# Arak-ADC.net
KiCad netlist of a schematic drawn in Altium Designer
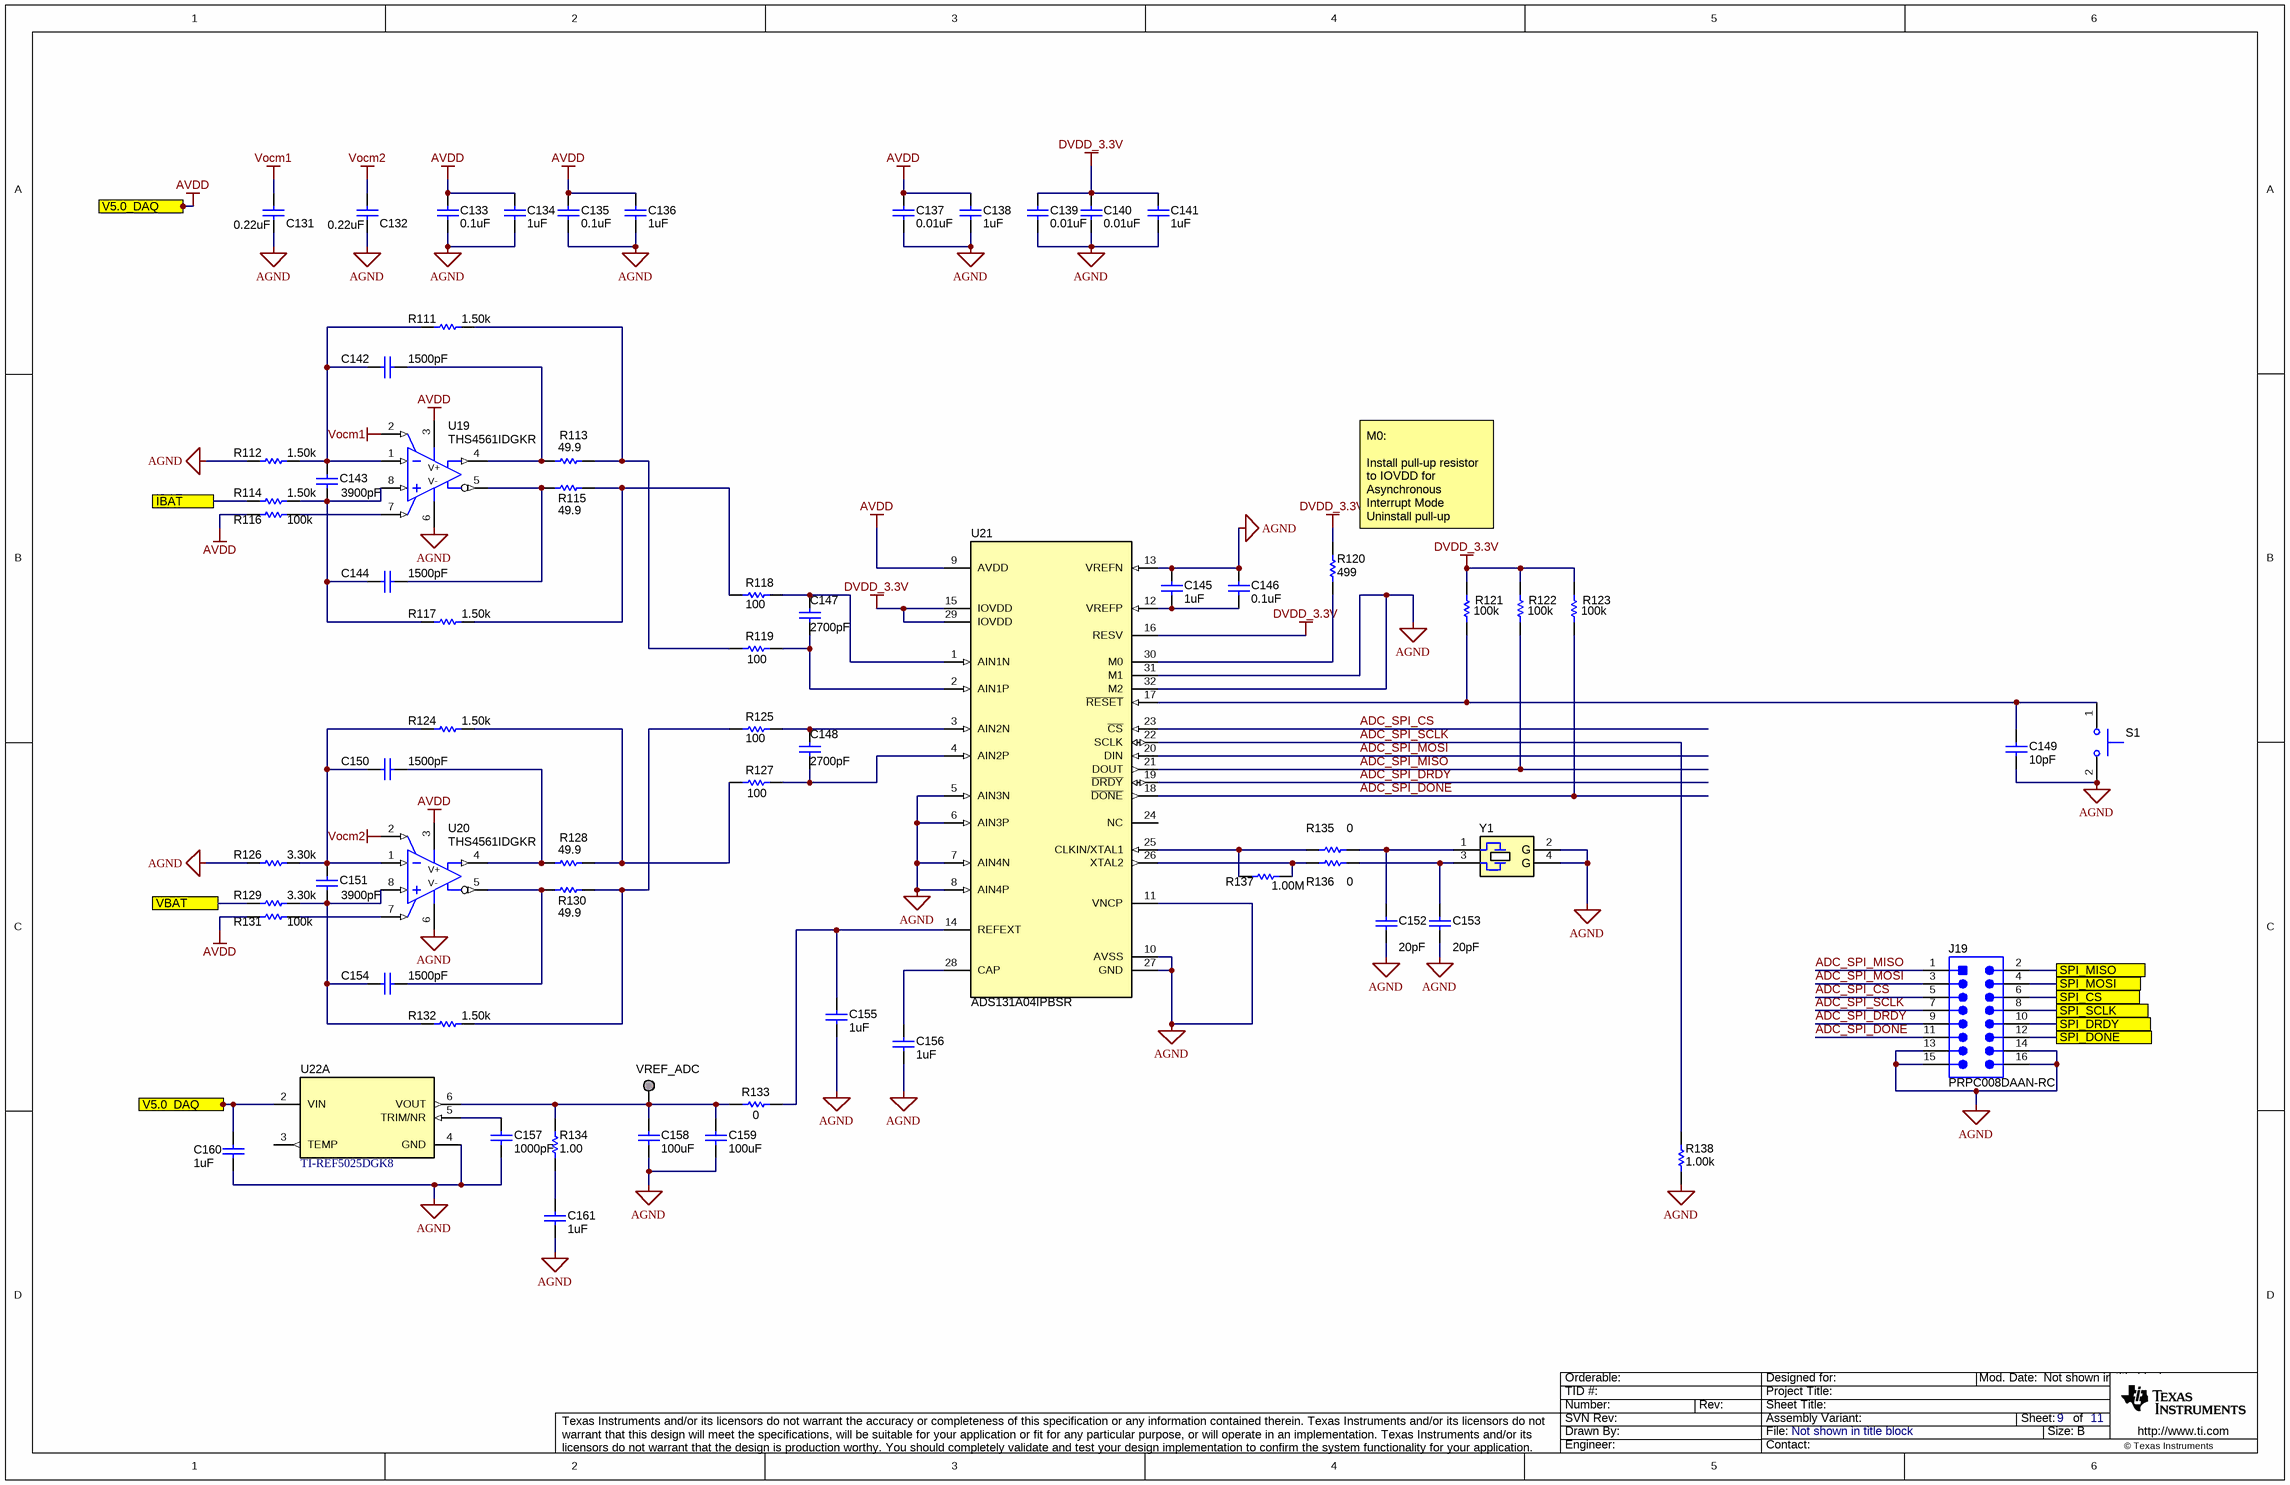
[diagram p0: Arak-ADC.SchDoc]

(export (version "E")
  (design (tool "Eeschema 10.0.6"))
  (components
    (comp (ref "C131")
      (value "Capacitor")
      (footprint "0603")
      (description "CAP, CERM, 0.22 uF, 16 V, +/- 10%, X7R, 0603")
      (fields
        (field (name "PARTNUMBER") "C0603C224K4RACTU")
        (field (name "VALUEDISPLAYED") "0.22uF")
        (field (name "MANUFACTURER") "Kemet")
        (field (name "PUBLISHER") "Texas Instruments")
      )
      (libsource (lib "Altium Vault - TI") (part "CMP-0006903-4"))
    )
    (comp (ref "C132")
      (value "Capacitor")
      (footprint "0603")
      (description "CAP, CERM, 0.22 uF, 16 V, +/- 10%, X7R, 0603")
      (fields
        (field (name "PARTNUMBER") "C0603C224K4RACTU")
        (field (name "VALUEDISPLAYED") "0.22uF")
        (field (name "MANUFACTURER") "Kemet")
        (field (name "PUBLISHER") "Texas Instruments")
      )
      (libsource (lib "Altium Vault - TI") (part "CMP-0006903-4"))
    )
    (comp (ref "C133")
      (value "Capacitor")
      (footprint "0603")
      (description "CAP, CERM, 0.1 uF, 25 V, +/- 5%, X7R, 0603")
      (fields
        (field (name "PARTNUMBER") "06033C104JAT2A")
        (field (name "VALUEDISPLAYED") "0.1uF")
        (field (name "MANUFACTURER") "AVX")
        (field (name "PUBLISHER") "Texas Instruments")
      )
      (libsource (lib "Altium Vault - TI") (part "CMP-0006752-5"))
    )
    (comp (ref "C134")
      (value "Capacitor")
      (footprint "0603")
      (description "CAP, CERM, 1 uF, 25 V, +/- 10%, X7R, 0603")
      (fields
        (field (name "PARTNUMBER") "GRM188R71E105KA12D")
        (field (name "VALUEDISPLAYED") "1uF")
        (field (name "MANUFACTURER") "MuRata")
        (field (name "PUBLISHER") "Texas Instruments")
      )
      (libsource (lib "Altium Vault - TI") (part "CMP-0007405-4"))
    )
    (comp (ref "C135")
      (value "Capacitor")
      (footprint "0603")
      (description "CAP, CERM, 0.1 uF, 25 V, +/- 5%, X7R, 0603")
      (fields
        (field (name "PARTNUMBER") "06033C104JAT2A")
        (field (name "VALUEDISPLAYED") "0.1uF")
        (field (name "MANUFACTURER") "AVX")
        (field (name "PUBLISHER") "Texas Instruments")
      )
      (libsource (lib "Altium Vault - TI") (part "CMP-0006752-5"))
    )
    (comp (ref "C136")
      (value "Capacitor")
      (footprint "0603")
      (description "CAP, CERM, 1 uF, 25 V, +/- 10%, X7R, 0603")
      (fields
        (field (name "PARTNUMBER") "GRM188R71E105KA12D")
        (field (name "VALUEDISPLAYED") "1uF")
        (field (name "MANUFACTURER") "MuRata")
        (field (name "PUBLISHER") "Texas Instruments")
      )
      (libsource (lib "Altium Vault - TI") (part "CMP-0007405-4"))
    )
    (comp (ref "C137")
      (value "Capacitor")
      (footprint "0603")
      (description "CAP, CERM, 0.01 uF, 100 V, +/- 10%, X7R, 0603")
      (fields
        (field (name "PARTNUMBER") "06031C103KAT2A")
        (field (name "VALUEDISPLAYED") "0.01uF")
        (field (name "MANUFACTURER") "AVX")
        (field (name "PUBLISHER") "Texas Instruments")
      )
      (libsource (lib "Altium Vault - TI") (part "CMP-0006727-4"))
    )
    (comp (ref "C138")
      (value "Capacitor")
      (footprint "0603")
      (description "CAP, CERM, 1 uF, 25 V, +/- 10%, X7R, 0603")
      (fields
        (field (name "PARTNUMBER") "GRM188R71E105KA12D")
        (field (name "VALUEDISPLAYED") "1uF")
        (field (name "MANUFACTURER") "MuRata")
        (field (name "PUBLISHER") "Texas Instruments")
      )
      (libsource (lib "Altium Vault - TI") (part "CMP-0007405-4"))
    )
    (comp (ref "C139")
      (value "Capacitor")
      (footprint "0603")
      (description "CAP, CERM, 0.01 uF, 100 V, +/- 10%, X7R, 0603")
      (fields
        (field (name "PARTNUMBER") "06031C103KAT2A")
        (field (name "VALUEDISPLAYED") "0.01uF")
        (field (name "MANUFACTURER") "AVX")
        (field (name "PUBLISHER") "Texas Instruments")
      )
      (libsource (lib "Altium Vault - TI") (part "CMP-0006727-4"))
    )
    (comp (ref "C140")
      (value "Capacitor")
      (footprint "0603")
      (description "CAP, CERM, 0.01 uF, 100 V, +/- 10%, X7R, 0603")
      (fields
        (field (name "PARTNUMBER") "06031C103KAT2A")
        (field (name "VALUEDISPLAYED") "0.01uF")
        (field (name "MANUFACTURER") "AVX")
        (field (name "PUBLISHER") "Texas Instruments")
      )
      (libsource (lib "Altium Vault - TI") (part "CMP-0006727-4"))
    )
    (comp (ref "C141")
      (value "Capacitor")
      (footprint "0603")
      (description "CAP, CERM, 1 uF, 25 V, +/- 10%, X7R, 0603")
      (fields
        (field (name "PARTNUMBER") "GRM188R71E105KA12D")
        (field (name "VALUEDISPLAYED") "1uF")
        (field (name "MANUFACTURER") "MuRata")
        (field (name "PUBLISHER") "Texas Instruments")
      )
      (libsource (lib "Altium Vault - TI") (part "CMP-0007405-4"))
    )
    (comp (ref "C142")
      (value "Capacitor")
      (footprint "0603")
      (description "CAP, CERM, 1500 pF, 100 V, +/- 5%, X7R, 0603")
      (fields
        (field (name "PARTNUMBER") "06031C152JAT2A")
        (field (name "VALUEDISPLAYED") "1500pF")
        (field (name "MANUFACTURER") "AVX")
        (field (name "PUBLISHER") "Texas Instruments")
      )
      (libsource (lib "Altium Vault - TI") (part "Capacitor"))
    )
    (comp (ref "C143")
      (value "GRM188R72A392KA01D")
      (footprint "0603")
      (description "CAP, CERM, 3900 pF, 100 V, +/- 10%, X7R, 0603")
      (fields
        (field (name "MANUFACTURER") "MuRata")
        (field (name "VALUEDISPLAYED") "3900pF")
        (field (name "PUBLISHER") "Texas Instruments")
      )
      (libsource (lib "Altium Vault - TI") (part "CMP-0007481-5"))
    )
    (comp (ref "C144")
      (value "Capacitor")
      (footprint "0603")
      (description "CAP, CERM, 1500 pF, 100 V, +/- 5%, X7R, 0603")
      (fields
        (field (name "PARTNUMBER") "06031C152JAT2A")
        (field (name "VALUEDISPLAYED") "1500pF")
        (field (name "MANUFACTURER") "AVX")
        (field (name "PUBLISHER") "Texas Instruments")
      )
      (libsource (lib "Altium Vault - TI") (part "Capacitor"))
    )
    (comp (ref "C145")
      (value "Capacitor")
      (footprint "0603")
      (description "CAP, CERM, 1 uF, 25 V, +/- 10%, X7R, 0603")
      (fields
        (field (name "PARTNUMBER") "GRM188R71E105KA12D")
        (field (name "VALUEDISPLAYED") "1uF")
        (field (name "MANUFACTURER") "MuRata")
        (field (name "PUBLISHER") "Texas Instruments")
      )
      (libsource (lib "Altium Vault - TI") (part "Capacitor"))
    )
    (comp (ref "C146")
      (value "Capacitor")
      (footprint "0603")
      (description "CAP, CERM, 0.1 uF, 25 V, +/- 5%, X7R, 0603")
      (fields
        (field (name "PARTNUMBER") "06033C104JAT2A")
        (field (name "VALUEDISPLAYED") "0.1uF")
        (field (name "MANUFACTURER") "AVX")
        (field (name "PUBLISHER") "Texas Instruments")
      )
      (libsource (lib "Altium Vault - TI") (part "Capacitor"))
    )
    (comp (ref "C147")
      (value "Capacitor")
      (footprint "0603")
      (description "CAP, CERM, 2700 pF, 50 V, +/- 5%, C0G/NP0, 0603")
      (fields
        (field (name "PARTNUMBER") "GRM1885C1H272JA01D")
        (field (name "VALUEDISPLAYED") "2700pF")
        (field (name "MANUFACTURER") "MuRata")
        (field (name "PUBLISHER") "Texas Instruments")
      )
      (libsource (lib "Altium Vault - TI") (part "Capacitor"))
    )
    (comp (ref "C148")
      (value "Capacitor")
      (footprint "0603")
      (description "CAP, CERM, 2700 pF, 50 V, +/- 5%, C0G/NP0, 0603")
      (fields
        (field (name "PARTNUMBER") "GRM1885C1H272JA01D")
        (field (name "VALUEDISPLAYED") "2700pF")
        (field (name "MANUFACTURER") "MuRata")
        (field (name "PUBLISHER") "Texas Instruments")
      )
      (libsource (lib "Altium Vault - TI") (part "Capacitor"))
    )
    (comp (ref "C149")
      (value "Capacitor")
      (footprint "0603")
      (description "CAP, CERM, 10 pF, 50 V, +/- 5%, C0G/NP0, 0603")
      (fields
        (field (name "PARTNUMBER") "06035A100JAT2A")
        (field (name "VALUEDISPLAYED") "10pF")
        (field (name "MANUFACTURER") "AVX")
        (field (name "PUBLISHER") "Texas Instruments")
      )
      (libsource (lib "Altium Vault - TI") (part "Capacitor"))
    )
    (comp (ref "C150")
      (value "Capacitor")
      (footprint "0603")
      (description "CAP, CERM, 1500 pF, 100 V, +/- 5%, X7R, 0603")
      (fields
        (field (name "PARTNUMBER") "06031C152JAT2A")
        (field (name "VALUEDISPLAYED") "1500pF")
        (field (name "MANUFACTURER") "AVX")
        (field (name "PUBLISHER") "Texas Instruments")
      )
      (libsource (lib "Altium Vault - TI") (part "Capacitor"))
    )
    (comp (ref "C151")
      (value "GRM188R72A392KA01D")
      (footprint "0603")
      (description "CAP, CERM, 3900 pF, 100 V, +/- 10%, X7R, 0603")
      (fields
        (field (name "MANUFACTURER") "MuRata")
        (field (name "VALUEDISPLAYED") "3900pF")
        (field (name "PUBLISHER") "Texas Instruments")
      )
      (libsource (lib "Altium Vault - TI") (part "CMP-0007481-5"))
    )
    (comp (ref "C152")
      (value "GRM1885C1H200JA01D")
      (footprint "0603")
      (description "CAP, CERM, 20 pF, 50 V, +/- 5%, C0G/NP0, 0603")
      (fields
        (field (name "MANUFACTURER") "MuRata")
        (field (name "VALUEDISPLAYED") "20pF")
        (field (name "PUBLISHER") "Texas Instruments")
      )
      (libsource (lib "Altium Vault - TI") (part "CMP-0007193-4"))
    )
    (comp (ref "C153")
      (value "GRM1885C1H200JA01D")
      (footprint "0603")
      (description "CAP, CERM, 20 pF, 50 V, +/- 5%, C0G/NP0, 0603")
      (fields
        (field (name "MANUFACTURER") "MuRata")
        (field (name "VALUEDISPLAYED") "20pF")
        (field (name "PUBLISHER") "Texas Instruments")
      )
      (libsource (lib "Altium Vault - TI") (part "CMP-0007193-4"))
    )
    (comp (ref "C154")
      (value "Capacitor")
      (footprint "0603")
      (description "CAP, CERM, 1500 pF, 100 V, +/- 5%, X7R, 0603")
      (fields
        (field (name "PARTNUMBER") "06031C152JAT2A")
        (field (name "VALUEDISPLAYED") "1500pF")
        (field (name "MANUFACTURER") "AVX")
        (field (name "PUBLISHER") "Texas Instruments")
      )
      (libsource (lib "Altium Vault - TI") (part "Capacitor"))
    )
    (comp (ref "C155")
      (value "Capacitor")
      (footprint "0603")
      (description "CAP, CERM, 1 uF, 25 V, +/- 10%, X7R, 0603")
      (fields
        (field (name "PARTNUMBER") "GRM188R71E105KA12D")
        (field (name "VALUEDISPLAYED") "1uF")
        (field (name "MANUFACTURER") "MuRata")
        (field (name "PUBLISHER") "Texas Instruments")
      )
      (libsource (lib "Altium Vault - TI") (part "Capacitor"))
    )
    (comp (ref "C156")
      (value "Capacitor")
      (footprint "0603")
      (description "CAP, CERM, 1 uF, 25 V, +/- 10%, X7R, 0603")
      (fields
        (field (name "PARTNUMBER") "GRM188R71E105KA12D")
        (field (name "VALUEDISPLAYED") "1uF")
        (field (name "MANUFACTURER") "MuRata")
        (field (name "PUBLISHER") "Texas Instruments")
      )
      (libsource (lib "Altium Vault - TI") (part "Capacitor"))
    )
    (comp (ref "C157")
      (value "Capacitor")
      (footprint "0603")
      (description "CAP, CERM, 1000 pF, 100 V, +/- 5%, X7R, 0603")
      (fields
        (field (name "PARTNUMBER") "06031C102JAT2A")
        (field (name "VALUEDISPLAYED") "1000pF")
        (field (name "MANUFACTURER") "AVX")
        (field (name "PUBLISHER") "Texas Instruments")
      )
      (libsource (lib "Altium Vault - TI") (part "Capacitor"))
    )
    (comp (ref "C158")
      (value "Capacitor")
      (footprint "1206_190")
      (description "CAP, CERM, 100 uF, 10 V, +/- 20%, X5R, 1206_190")
      (fields
        (field (name "PARTNUMBER") "C3216X5R1A107M160AC")
        (field (name "VALUEDISPLAYED") "100uF")
        (field (name "MANUFACTURER") "TDK")
        (field (name "PUBLISHER") "Texas Instruments")
      )
      (libsource (lib "Altium Vault - TI") (part "Capacitor"))
    )
    (comp (ref "C159")
      (value "Capacitor")
      (footprint "1206_190")
      (description "CAP, CERM, 100 uF, 10 V, +/- 20%, X5R, 1206_190")
      (fields
        (field (name "PARTNUMBER") "C3216X5R1A107M160AC")
        (field (name "VALUEDISPLAYED") "100uF")
        (field (name "MANUFACTURER") "TDK")
        (field (name "PUBLISHER") "Texas Instruments")
      )
      (libsource (lib "Altium Vault - TI") (part "Capacitor"))
    )
    (comp (ref "C160")
      (value "Capacitor")
      (footprint "0603")
      (description "CAP, CERM, 1 uF, 25 V, +/- 10%, X7R, 0603")
      (fields
        (field (name "PARTNUMBER") "GRM188R71E105KA12D")
        (field (name "VALUEDISPLAYED") "1uF")
        (field (name "MANUFACTURER") "MuRata")
        (field (name "PUBLISHER") "Texas Instruments")
      )
      (libsource (lib "Altium Vault - TI") (part "Capacitor"))
    )
    (comp (ref "C161")
      (value "Capacitor")
      (footprint "0603")
      (description "CAP, CERM, 1 uF, 25 V, +/- 10%, X7R, 0603")
      (fields
        (field (name "PARTNUMBER") "GRM188R71E105KA12D")
        (field (name "VALUEDISPLAYED") "1uF")
        (field (name "MANUFACTURER") "MuRata")
        (field (name "PUBLISHER") "Texas Instruments")
      )
      (libsource (lib "Altium Vault - TI") (part "Capacitor"))
    )
    (comp (ref "J19")
      (value "PRPC008DAAN-RC")
      (footprint "Sullins_xxxC008DAAN")
      (description "Header, 2.54mm, 8x2, Gold, TH")
      (fields
        (field (name "MANUFACTURER") "Sullins Connector Solutions")
        (field (name "PUBLISHER") "Texas Instruments")
      )
      (libsource (lib "Altium Vault - TI") (part "CMP-0054590-1"))
    )
    (comp (ref "R111")
      (value "RC0603FR-071K5L")
      (footprint "0603")
      (description "RES, 1.50 k, 1%, 0.1 W, 0603")
      (fields
        (field (name "MANUFACTURER") "Yageo America")
        (field (name "VALUEDISPLAYED") "1.50k")
        (field (name "PUBLISHER") "Texas Instruments")
      )
      (libsource (lib "Altium Vault - TI") (part "CMP-0022883-3"))
    )
    (comp (ref "R112")
      (value "RC0603FR-071K5L")
      (footprint "0603")
      (description "RES, 1.50 k, 1%, 0.1 W, 0603")
      (fields
        (field (name "MANUFACTURER") "Yageo America")
        (field (name "VALUEDISPLAYED") "1.50k")
        (field (name "PUBLISHER") "Texas Instruments")
      )
      (libsource (lib "Altium Vault - TI") (part "CMP-0022883-3"))
    )
    (comp (ref "R113")
      (value "Resistor")
      (footprint "0603")
      (description "RES, 49.9, 1%, 0.1 W, AEC-Q200 Grade 0, 0603")
      (fields
        (field (name "PARTNUMBER") "CRCW060349R9FKEA")
        (field (name "MANUFACTURER") "Vishay-Dale")
        (field (name "VALUEDISPLAYED") "49.9")
      )
      (libsource (lib "Altium Vault - TI") (part "CMP-0022448-4"))
    )
    (comp (ref "R114")
      (value "RC0603FR-071K5L")
      (footprint "0603")
      (description "RES, 1.50 k, 1%, 0.1 W, 0603")
      (fields
        (field (name "MANUFACTURER") "Yageo America")
        (field (name "VALUEDISPLAYED") "1.50k")
        (field (name "PUBLISHER") "Texas Instruments")
      )
      (libsource (lib "Altium Vault - TI") (part "CMP-0022883-3"))
    )
    (comp (ref "R115")
      (value "Resistor")
      (footprint "0603")
      (description "RES, 49.9, 1%, 0.1 W, AEC-Q200 Grade 0, 0603")
      (fields
        (field (name "PARTNUMBER") "CRCW060349R9FKEA")
        (field (name "MANUFACTURER") "Vishay-Dale")
        (field (name "VALUEDISPLAYED") "49.9")
      )
      (libsource (lib "Altium Vault - TI") (part "CMP-0022448-4"))
    )
    (comp (ref "R116")
      (value "Resistor")
      (footprint "0603")
      (description "RES, 100 k, 1%, 0.1 W, AEC-Q200 Grade 0, 0603")
      (fields
        (field (name "PARTNUMBER") "CRCW0603100KFKEA")
        (field (name "MANUFACTURER") "Vishay-Dale")
        (field (name "VALUEDISPLAYED") "100k")
      )
      (libsource (lib "Altium Vault - TI") (part "CMP-0021990-4"))
    )
    (comp (ref "R117")
      (value "RC0603FR-071K5L")
      (footprint "0603")
      (description "RES, 1.50 k, 1%, 0.1 W, 0603")
      (fields
        (field (name "MANUFACTURER") "Yageo America")
        (field (name "VALUEDISPLAYED") "1.50k")
        (field (name "PUBLISHER") "Texas Instruments")
      )
      (libsource (lib "Altium Vault - TI") (part "CMP-0022883-3"))
    )
    (comp (ref "R118")
      (value "Resistor")
      (footprint "0603")
      (description "RES, 100, 1%, 0.1 W, AEC-Q200 Grade 0, 0603")
      (fields
        (field (name "PARTNUMBER") "CRCW0603100RFKEA")
        (field (name "MANUFACTURER") "Vishay-Dale")
        (field (name "VALUEDISPLAYED") "100")
      )
      (libsource (lib "Altium Vault - TI") (part "CMP-0021991-4"))
    )
    (comp (ref "R119")
      (value "Resistor")
      (footprint "0603")
      (description "RES, 100, 1%, 0.1 W, AEC-Q200 Grade 0, 0603")
      (fields
        (field (name "PARTNUMBER") "CRCW0603100RFKEA")
        (field (name "MANUFACTURER") "Vishay-Dale")
        (field (name "VALUEDISPLAYED") "100")
      )
      (libsource (lib "Altium Vault - TI") (part "CMP-0021991-4"))
    )
    (comp (ref "R120")
      (value "Resistor")
      (footprint "0603")
      (description "RES, 499, 1%, 0.1 W, AEC-Q200 Grade 0, 0603")
      (fields
        (field (name "PARTNUMBER") "CRCW0603499RFKEA")
        (field (name "MANUFACTURER") "Vishay-Dale")
        (field (name "VALUEDISPLAYED") "499")
      )
      (libsource (lib "Altium Vault - TI") (part "CMP-0022446-5"))
    )
    (comp (ref "R121")
      (value "Resistor")
      (footprint "0603")
      (description "RES, 100 k, 1%, 0.1 W, AEC-Q200 Grade 0, 0603")
      (fields
        (field (name "PARTNUMBER") "CRCW0603100KFKEA")
        (field (name "MANUFACTURER") "Vishay-Dale")
        (field (name "VALUEDISPLAYED") "100k")
      )
      (libsource (lib "Altium Vault - TI") (part "CMP-0021990-4"))
    )
    (comp (ref "R122")
      (value "Resistor")
      (footprint "0603")
      (description "RES, 100 k, 1%, 0.1 W, AEC-Q200 Grade 0, 0603")
      (fields
        (field (name "PARTNUMBER") "CRCW0603100KFKEA")
        (field (name "MANUFACTURER") "Vishay-Dale")
        (field (name "VALUEDISPLAYED") "100k")
      )
      (libsource (lib "Altium Vault - TI") (part "CMP-0021990-4"))
    )
    (comp (ref "R123")
      (value "Resistor")
      (footprint "0603")
      (description "RES, 100 k, 1%, 0.1 W, AEC-Q200 Grade 0, 0603")
      (fields
        (field (name "PARTNUMBER") "CRCW0603100KFKEA")
        (field (name "MANUFACTURER") "Vishay-Dale")
        (field (name "VALUEDISPLAYED") "100k")
      )
      (libsource (lib "Altium Vault - TI") (part "CMP-0021990-4"))
    )
    (comp (ref "R124")
      (value "RC0603FR-071K5L")
      (footprint "0603")
      (description "RES, 1.50 k, 1%, 0.1 W, 0603")
      (fields
        (field (name "MANUFACTURER") "Yageo America")
        (field (name "VALUEDISPLAYED") "1.50k")
        (field (name "PUBLISHER") "Texas Instruments")
      )
      (libsource (lib "Altium Vault - TI") (part "CMP-0022883-3"))
    )
    (comp (ref "R125")
      (value "Resistor")
      (footprint "0603")
      (description "RES, 100, 1%, 0.1 W, AEC-Q200 Grade 0, 0603")
      (fields
        (field (name "PARTNUMBER") "CRCW0603100RFKEA")
        (field (name "MANUFACTURER") "Vishay-Dale")
        (field (name "VALUEDISPLAYED") "100")
      )
      (libsource (lib "Altium Vault - TI") (part "CMP-0021991-4"))
    )
    (comp (ref "R126")
      (value "RC0603FR-073K3L")
      (footprint "0603")
      (description "RES, 3.30 k, 1%, 0.1 W, 0603")
      (fields
        (field (name "VALUEDISPLAYED") "3.30k")
        (field (name "MANUFACTURER") "Yageo America")
        (field (name "PUBLISHER") "Texas Instruments")
      )
      (libsource (lib "Altium Vault - TI") (part "Resistor"))
    )
    (comp (ref "R127")
      (value "Resistor")
      (footprint "0603")
      (description "RES, 100, 1%, 0.1 W, AEC-Q200 Grade 0, 0603")
      (fields
        (field (name "PARTNUMBER") "CRCW0603100RFKEA")
        (field (name "MANUFACTURER") "Vishay-Dale")
        (field (name "VALUEDISPLAYED") "100")
      )
      (libsource (lib "Altium Vault - TI") (part "CMP-0021991-4"))
    )
    (comp (ref "R128")
      (value "Resistor")
      (footprint "0603")
      (description "RES, 49.9, 1%, 0.1 W, AEC-Q200 Grade 0, 0603")
      (fields
        (field (name "PARTNUMBER") "CRCW060349R9FKEA")
        (field (name "MANUFACTURER") "Vishay-Dale")
        (field (name "VALUEDISPLAYED") "49.9")
      )
      (libsource (lib "Altium Vault - TI") (part "CMP-0022448-4"))
    )
    (comp (ref "R129")
      (value "RC0603FR-073K3L")
      (footprint "0603")
      (description "RES, 3.30 k, 1%, 0.1 W, 0603")
      (fields
        (field (name "VALUEDISPLAYED") "3.30k")
        (field (name "MANUFACTURER") "Yageo America")
        (field (name "PUBLISHER") "Texas Instruments")
      )
      (libsource (lib "Altium Vault - TI") (part "Resistor"))
    )
    (comp (ref "R130")
      (value "Resistor")
      (footprint "0603")
      (description "RES, 49.9, 1%, 0.1 W, AEC-Q200 Grade 0, 0603")
      (fields
        (field (name "PARTNUMBER") "CRCW060349R9FKEA")
        (field (name "MANUFACTURER") "Vishay-Dale")
        (field (name "VALUEDISPLAYED") "49.9")
      )
      (libsource (lib "Altium Vault - TI") (part "Resistor"))
    )
    (comp (ref "R131")
      (value "Resistor")
      (footprint "0603")
      (description "RES, 100 k, 1%, 0.1 W, AEC-Q200 Grade 0, 0603")
      (fields
        (field (name "PARTNUMBER") "CRCW0603100KFKEA")
        (field (name "MANUFACTURER") "Vishay-Dale")
        (field (name "VALUEDISPLAYED") "100k")
      )
      (libsource (lib "Altium Vault - TI") (part "Resistor"))
    )
    (comp (ref "R132")
      (value "RC0603FR-071K5L")
      (footprint "0603")
      (description "RES, 1.50 k, 1%, 0.1 W, 0603")
      (fields
        (field (name "MANUFACTURER") "Yageo America")
        (field (name "VALUEDISPLAYED") "1.50k")
        (field (name "PUBLISHER") "Texas Instruments")
      )
      (libsource (lib "Altium Vault - TI") (part "Resistor"))
    )
    (comp (ref "R133")
      (value "Resistor")
      (footprint "0603")
      (description "RES, 0, 5%, 0.1 W, 0603")
      (fields
        (field (name "PARTNUMBER") "ERJ-3GEY0R00V")
        (field (name "MANUFACTURER") "Panasonic")
        (field (name "VALUEDISPLAYED") "0")
        (field (name "PUBLISHER") "Texas Instruments")
      )
      (libsource (lib "Altium Vault - TI") (part "Resistor"))
    )
    (comp (ref "R134")
      (value "Resistor")
      (footprint "0603")
      (description "RES, 1.00, 1%, 0.1 W, AEC-Q200 Grade 0, 0603")
      (fields
        (field (name "PARTNUMBER") "CRCW06031R00FKEA")
        (field (name "VALUEDISPLAYED") "1.00")
        (field (name "MANUFACTURER") "Vishay-Dale")
      )
      (libsource (lib "Altium Vault - TI") (part "Resistor"))
    )
    (comp (ref "R135")
      (value "Resistor")
      (footprint "0603")
      (description "RES, 0, 5%, 0.1 W, 0603")
      (fields
        (field (name "PARTNUMBER") "ERJ-3GEY0R00V")
        (field (name "MANUFACTURER") "Panasonic")
        (field (name "VALUEDISPLAYED") "0")
        (field (name "PUBLISHER") "Texas Instruments")
      )
      (libsource (lib "Altium Vault - TI") (part "CMP-0025874-3"))
    )
    (comp (ref "R136")
      (value "Resistor")
      (footprint "0603")
      (description "RES, 0, 5%, 0.1 W, 0603")
      (fields
        (field (name "PARTNUMBER") "ERJ-3GEY0R00V")
        (field (name "MANUFACTURER") "Panasonic")
        (field (name "VALUEDISPLAYED") "0")
        (field (name "PUBLISHER") "Texas Instruments")
      )
      (libsource (lib "Altium Vault - TI") (part "CMP-0025874-3"))
    )
    (comp (ref "R137")
      (value "Resistor")
      (footprint "0603")
      (description "RES, 1.00 M, 1%, 0.1 W, AEC-Q200 Grade 0, 0603")
      (fields
        (field (name "PARTNUMBER") "CRCW06031M00FKEA")
        (field (name "MANUFACTURER") "Vishay-Dale")
        (field (name "VALUEDISPLAYED") "1.00M")
      )
      (libsource (lib "Altium Vault - TI") (part "CMP-0022138-4"))
    )
    (comp (ref "R138")
      (value "Resistor")
      (footprint "0603")
      (description "RES, 1.00 k, 1%, 0.1 W, AEC-Q200 Grade 0, 0603")
      (fields
        (field (name "PARTNUMBER") "CRCW06031K00FKEA")
        (field (name "MANUFACTURER") "Vishay-Dale")
        (field (name "VALUEDISPLAYED") "1.00k")
      )
      (libsource (lib "Altium Vault - TI") (part "CMP-0022109-5"))
    )
    (comp (ref "S1")
      (value "Switch_PushButton")
      (footprint "SW_TL1015AF160QG")
      (description "Switch, Tactile, SPST-NO, 0.05A, 12V, SMT")
      (fields
        (field (name "PARTNUMBER") "TL1015AF160QG")
        (field (name "MANUFACTURER") "E-Switch")
        (field (name "PUBLISHER") "Texas Instruments")
      )
      (libsource (lib "Altium Vault - TI") (part "Switch_PushButton"))
    )
    (comp (ref "U19")
      (value "THS4561IDGKR")
      (footprint "DGK0008A_N")
      (description "Low-Power, High Supply Range, 60-MHz, Fully Differential Amplifier, DGK0008A (VSSOP-8)")
      (fields
        (field (name "ALTERNATE PARTNUMBER") "THS4561IDGKT")
        (field (name "MANUFACTURER") "Texas Instruments")
        (field (name "PARTNUMBER") "THS4561IDGKR")
        (field (name "PUBLISHER") "Texas Instruments")
      )
      (libsource (lib "Altium Vault - TI") (part "CMP-0074888-1"))
    )
    (comp (ref "U20")
      (value "THS4561IDGKR")
      (footprint "DGK0008A_N")
      (description "Low-Power, High Supply Range, 60-MHz, Fully Differential Amplifier, DGK0008A (VSSOP-8)")
      (fields
        (field (name "ALTERNATE PARTNUMBER") "THS4561IDGKT")
        (field (name "MANUFACTURER") "Texas Instruments")
        (field (name "PARTNUMBER") "THS4561IDGKR")
        (field (name "PUBLISHER") "Texas Instruments")
      )
      (libsource (lib "Altium Vault - TI") (part "CMP-0074888-1"))
    )
    (comp (ref "U21")
      (value "ADS131A04IPBSR")
      (footprint "PBS0032A_L")
      (description "24-Bit, 128kSPS, 4-Ch, Simultaneous Sampling, Delta-Sigma ADC, PBS0032A (TQFP-32)")
      (fields
        (field (name "ALTERNATE PARTNUMBER") "ADS131A04IPBS")
        (field (name "PARTNUMBER") "ADS131A04IPBSR")
        (field (name "MANUFACTURER") "Texas Instruments")
        (field (name "PUBLISHER") "Texas Instruments")
      )
      (libsource (lib "Altium Vault - TI") (part "ADS131A04"))
    )
    (comp (ref "U22")
      (value "TI-REF5025DGK8")
      (footprint "DGK0008A_N")
      (fields (field (name "PARTNUMBER") "REF5025IDGKR") (field (name "MANUFACTURER") "Texas Instruments"))
      (libsource (lib "Altium Vault - TI") (part "CMP-0032584-1"))
    )
    (comp (ref "VREF_ADC")
      (value "Pogo Pad")
      (footprint "PogoPad")
      (description "Pad for Pogo Pin Connector")
      (fields (field (name "SYMBOLCREATOR") "codlsc") (field (name "PUBLISHER") "Texas Instruments"))
      (libsource (lib "MiscParts") (part "PogoPad"))
    )
    (comp (ref "Y1")
      (value "XTAL_4P_13_G24")
      (footprint "CTS_407")
      (description "Crystal, 16.384 MHz, 20 pF, SMD")
      (fields
        (field (name "PARTNUMBER") "407F35E016M3840")
        (field (name "MANUFACTURER") "CTS Electrocomponents")
      )
      (libsource (lib "Altium Vault - TI") (part "XTAL_4P_13_G24"))
    )
  )
  (nets
    (net (code "1") (name "/ADC_SPI_CS") (class "Default")
      (node (ref "J19") (pin "5") (pinfunction "5_5") (pintype "passive"))
      (node (ref "U21") (pin "23") (pinfunction "CS_23") (pintype "input"))
    )
    (net (code "2") (name "/ADC_SPI_DONE") (class "Default")
      (node (ref "J19") (pin "11") (pinfunction "11_11") (pintype "passive"))
      (node (ref "R123") (pin "1") (pinfunction "1_1") (pintype "passive"))
      (node (ref "U21") (pin "18") (pinfunction "DONE_18") (pintype "output"))
    )
    (net (code "3") (name "/ADC_SPI_DRDY") (class "Default")
      (node (ref "J19") (pin "9") (pinfunction "9_9") (pintype "passive"))
      (node (ref "U21") (pin "19") (pinfunction "DRDY_19") (pintype "bidirectional"))
    )
    (net (code "4") (name "/ADC_SPI_MISO") (class "Default")
      (node (ref "J19") (pin "1") (pinfunction "1_1") (pintype "passive"))
      (node (ref "R122") (pin "1") (pinfunction "1_1") (pintype "passive"))
      (node (ref "U21") (pin "21") (pinfunction "DOUT_21") (pintype "output"))
    )
    (net (code "5") (name "/ADC_SPI_MOSI") (class "Default")
      (node (ref "J19") (pin "3") (pinfunction "3_3") (pintype "passive"))
      (node (ref "U21") (pin "20") (pinfunction "DIN_20") (pintype "input"))
    )
    (net (code "6") (name "/ADC_SPI_SCLK") (class "Default")
      (node (ref "J19") (pin "7") (pinfunction "7_7") (pintype "passive"))
      (node (ref "R138") (pin "2") (pinfunction "2_2") (pintype "passive"))
      (node (ref "U21") (pin "22") (pinfunction "SCLK_22") (pintype "bidirectional"))
    )
    (net (code "7") (name "/IBAT") (class "Default")
      (node (ref "R114") (pin "1") (pinfunction "1_1") (pintype "passive"))
    )
    (net (code "8") (name "/SPI_CS") (class "Default")
      (node (ref "J19") (pin "6") (pinfunction "6_6") (pintype "passive"))
    )
    (net (code "9") (name "/SPI_DONE") (class "Default")
      (node (ref "J19") (pin "12") (pinfunction "12_12") (pintype "passive"))
    )
    (net (code "10") (name "/SPI_DRDY") (class "Default")
      (node (ref "J19") (pin "10") (pinfunction "10_10") (pintype "passive"))
    )
    (net (code "11") (name "/SPI_MISO") (class "Default")
      (node (ref "J19") (pin "2") (pinfunction "2_2") (pintype "passive"))
    )
    (net (code "12") (name "/SPI_MOSI") (class "Default")
      (node (ref "J19") (pin "4") (pinfunction "4_4") (pintype "passive"))
    )
    (net (code "13") (name "/SPI_SCLK") (class "Default")
      (node (ref "J19") (pin "8") (pinfunction "8_8") (pintype "passive"))
    )
    (net (code "14") (name "/VBAT") (class "Default")
      (node (ref "R129") (pin "1") (pinfunction "1_1") (pintype "passive"))
    )
    (net (code "15") (name "AGND") (class "Default")
      (node (ref "C131") (pin "2") (pinfunction "2_2") (pintype "passive"))
      (node (ref "C132") (pin "2") (pinfunction "2_2") (pintype "passive"))
      (node (ref "C133") (pin "2") (pinfunction "2_2") (pintype "passive"))
      (node (ref "C134") (pin "2") (pinfunction "2_2") (pintype "passive"))
      (node (ref "C135") (pin "2") (pinfunction "2_2") (pintype "passive"))
      (node (ref "C136") (pin "2") (pinfunction "2_2") (pintype "passive"))
      (node (ref "C137") (pin "2") (pinfunction "2_2") (pintype "passive"))
      (node (ref "C138") (pin "2") (pinfunction "2_2") (pintype "passive"))
      (node (ref "C139") (pin "2") (pinfunction "2_2") (pintype "passive"))
      (node (ref "C140") (pin "2") (pinfunction "2_2") (pintype "passive"))
      (node (ref "C141") (pin "2") (pinfunction "2_2") (pintype "passive"))
      (node (ref "C145") (pin "1") (pinfunction "1_1") (pintype "passive"))
      (node (ref "C146") (pin "1") (pinfunction "1_1") (pintype "passive"))
      (node (ref "C149") (pin "1") (pinfunction "1_1") (pintype "passive"))
      (node (ref "C152") (pin "2") (pinfunction "2_2") (pintype "passive"))
      (node (ref "C153") (pin "2") (pinfunction "2_2") (pintype "passive"))
      (node (ref "C155") (pin "2") (pinfunction "2_2") (pintype "passive"))
      (node (ref "C156") (pin "2") (pinfunction "2_2") (pintype "passive"))
      (node (ref "C157") (pin "2") (pinfunction "2_2") (pintype "passive"))
      (node (ref "C158") (pin "2") (pinfunction "2_2") (pintype "passive"))
      (node (ref "C159") (pin "2") (pinfunction "2_2") (pintype "passive"))
      (node (ref "C160") (pin "2") (pinfunction "2_2") (pintype "passive"))
      (node (ref "C161") (pin "2") (pinfunction "2_2") (pintype "passive"))
      (node (ref "J19") (pin "13") (pinfunction "13_13") (pintype "passive"))
      (node (ref "J19") (pin "14") (pinfunction "14_14") (pintype "passive"))
      (node (ref "J19") (pin "15") (pinfunction "15_15") (pintype "passive"))
      (node (ref "J19") (pin "16") (pinfunction "16_16") (pintype "passive"))
      (node (ref "R112") (pin "1") (pinfunction "1_1") (pintype "passive"))
      (node (ref "R126") (pin "1") (pinfunction "1_1") (pintype "passive"))
      (node (ref "R138") (pin "1") (pinfunction "1_1") (pintype "passive"))
      (node (ref "S1") (pin "2") (pinfunction "2_2") (pintype "passive"))
      (node (ref "U19") (pin "6") (pinfunction "VS-_6") (pintype "power_in"))
      (node (ref "U20") (pin "6") (pinfunction "VS-_6") (pintype "power_in"))
      (node (ref "U21") (pin "10") (pinfunction "AVSS_10") (pintype "power_in"))
      (node (ref "U21") (pin "11") (pinfunction "VNCP_11") (pintype "power_in"))
      (node (ref "U21") (pin "13") (pinfunction "VREFN_13") (pintype "input"))
      (node (ref "U21") (pin "27") (pinfunction "GND_27") (pintype "power_in"))
      (node (ref "U21") (pin "31") (pinfunction "M1_31") (pintype "passive"))
      (node (ref "U21") (pin "32") (pinfunction "M2_32") (pintype "passive"))
      (node (ref "U21") (pin "5") (pinfunction "AIN3N_5") (pintype "input"))
      (node (ref "U21") (pin "6") (pinfunction "AIN3P_6") (pintype "input"))
      (node (ref "U21") (pin "7") (pinfunction "AIN4N_7") (pintype "input"))
      (node (ref "U21") (pin "8") (pinfunction "AIN4P_8") (pintype "input"))
      (node (ref "U22") (pin "4") (pinfunction "GND_4") (pintype "power_in"))
      (node (ref "Y1") (pin "2") (pinfunction "GND_2") (pintype "power_in"))
      (node (ref "Y1") (pin "4") (pinfunction "GND_4") (pintype "power_in"))
    )
    (net (code "16") (name "AVDD") (class "Default")
      (node (ref "C133") (pin "1") (pinfunction "1_1") (pintype "passive"))
      (node (ref "C134") (pin "1") (pinfunction "1_1") (pintype "passive"))
      (node (ref "C135") (pin "1") (pinfunction "1_1") (pintype "passive"))
      (node (ref "C136") (pin "1") (pinfunction "1_1") (pintype "passive"))
      (node (ref "C137") (pin "1") (pinfunction "1_1") (pintype "passive"))
      (node (ref "C138") (pin "1") (pinfunction "1_1") (pintype "passive"))
      (node (ref "C160") (pin "1") (pinfunction "1_1") (pintype "passive"))
      (node (ref "R116") (pin "2") (pinfunction "2_2") (pintype "passive"))
      (node (ref "R131") (pin "2") (pinfunction "2_2") (pintype "passive"))
      (node (ref "U19") (pin "3") (pinfunction "VS+_3") (pintype "power_in"))
      (node (ref "U20") (pin "3") (pinfunction "VS+_3") (pintype "power_in"))
      (node (ref "U21") (pin "9") (pinfunction "AVDD_9") (pintype "power_in"))
      (node (ref "U22") (pin "2") (pinfunction "VIN_2") (pintype "power_in"))
    )
    (net (code "17") (name "DVDD_3.3V") (class "Default")
      (node (ref "C139") (pin "1") (pinfunction "1_1") (pintype "passive"))
      (node (ref "C140") (pin "1") (pinfunction "1_1") (pintype "passive"))
      (node (ref "C141") (pin "1") (pinfunction "1_1") (pintype "passive"))
      (node (ref "R120") (pin "2") (pinfunction "2_2") (pintype "passive"))
      (node (ref "R121") (pin "2") (pinfunction "2_2") (pintype "passive"))
      (node (ref "R122") (pin "2") (pinfunction "2_2") (pintype "passive"))
      (node (ref "R123") (pin "2") (pinfunction "2_2") (pintype "passive"))
      (node (ref "U21") (pin "15") (pinfunction "IOVDD_15") (pintype "power_in"))
      (node (ref "U21") (pin "16") (pinfunction "RESV_16") (pintype "passive"))
      (node (ref "U21") (pin "29") (pinfunction "IOVDD_29") (pintype "power_in"))
    )
    (net (code "18") (name "Net-(C152-Pad1)") (class "Default")
      (node (ref "C152") (pin "1") (pinfunction "1_1") (pintype "passive"))
      (node (ref "R135") (pin "2") (pinfunction "2_2") (pintype "passive"))
      (node (ref "Y1") (pin "1") (pinfunction "1_1") (pintype "passive"))
    )
    (net (code "19") (name "Net-(C153-Pad1)") (class "Default")
      (node (ref "C153") (pin "1") (pinfunction "1_1") (pintype "passive"))
      (node (ref "R136") (pin "1") (pinfunction "1_1") (pintype "passive"))
      (node (ref "Y1") (pin "3") (pinfunction "3_3") (pintype "passive"))
    )
    (net (code "20") (name "Net-(C161-Pad1)") (class "Default")
      (node (ref "C161") (pin "1") (pinfunction "1_1") (pintype "passive"))
      (node (ref "R134") (pin "1") (pinfunction "1_1") (pintype "passive"))
    )
    (net (code "21") (name "Net-(R111-Pad2)") (class "Default")
      (node (ref "R111") (pin "2") (pinfunction "2_2") (pintype "passive"))
      (node (ref "R113") (pin "2") (pinfunction "2_2") (pintype "passive"))
      (node (ref "R119") (pin "1") (pinfunction "1_1") (pintype "passive"))
    )
    (net (code "22") (name "Net-(R115-Pad2)") (class "Default")
      (node (ref "R115") (pin "2") (pinfunction "2_2") (pintype "passive"))
      (node (ref "R117") (pin "2") (pinfunction "2_2") (pintype "passive"))
      (node (ref "R118") (pin "1") (pinfunction "1_1") (pintype "passive"))
    )
    (net (code "23") (name "Net-(R124-Pad2)") (class "Default")
      (node (ref "R124") (pin "2") (pinfunction "2_2") (pintype "passive"))
      (node (ref "R127") (pin "1") (pinfunction "1_1") (pintype "passive"))
      (node (ref "R128") (pin "2") (pinfunction "2_2") (pintype "passive"))
    )
    (net (code "24") (name "Net-(R125-Pad1)") (class "Default")
      (node (ref "R125") (pin "1") (pinfunction "1_1") (pintype "passive"))
      (node (ref "R130") (pin "2") (pinfunction "2_2") (pintype "passive"))
      (node (ref "R132") (pin "2") (pinfunction "2_2") (pintype "passive"))
    )
    (net (code "25") (name "Net-(U19-VIN+)") (class "Default")
      (node (ref "C143") (pin "2") (pinfunction "2_2") (pintype "passive"))
      (node (ref "C144") (pin "1") (pinfunction "1_1") (pintype "passive"))
      (node (ref "R114") (pin "2") (pinfunction "2_2") (pintype "passive"))
      (node (ref "R117") (pin "1") (pinfunction "1_1") (pintype "passive"))
      (node (ref "U19") (pin "8") (pinfunction "VIN+_8") (pintype "input"))
    )
    (net (code "26") (name "Net-(U19-VIN-)") (class "Default")
      (node (ref "C142") (pin "1") (pinfunction "1_1") (pintype "passive"))
      (node (ref "C143") (pin "1") (pinfunction "1_1") (pintype "passive"))
      (node (ref "R111") (pin "1") (pinfunction "1_1") (pintype "passive"))
      (node (ref "R112") (pin "2") (pinfunction "2_2") (pintype "passive"))
      (node (ref "U19") (pin "1") (pinfunction "VIN-_1") (pintype "input"))
    )
    (net (code "27") (name "Net-(U19-VOUT+)") (class "Default")
      (node (ref "C142") (pin "2") (pinfunction "2_2") (pintype "passive"))
      (node (ref "R113") (pin "1") (pinfunction "1_1") (pintype "passive"))
      (node (ref "U19") (pin "4") (pinfunction "VOUT+_4") (pintype "output"))
    )
    (net (code "28") (name "Net-(U19-VOUT-)") (class "Default")
      (node (ref "C144") (pin "2") (pinfunction "2_2") (pintype "passive"))
      (node (ref "R115") (pin "1") (pinfunction "1_1") (pintype "passive"))
      (node (ref "U19") (pin "5") (pinfunction "VOUT-_5") (pintype "output"))
    )
    (net (code "29") (name "Net-(U19-~{PD})") (class "Default")
      (node (ref "R116") (pin "1") (pinfunction "1_1") (pintype "passive"))
      (node (ref "U19") (pin "7") (pinfunction "~{PD}_7") (pintype "input"))
    )
    (net (code "30") (name "Net-(U20-VIN+)") (class "Default")
      (node (ref "C151") (pin "2") (pinfunction "2_2") (pintype "passive"))
      (node (ref "C154") (pin "1") (pinfunction "1_1") (pintype "passive"))
      (node (ref "R129") (pin "2") (pinfunction "2_2") (pintype "passive"))
      (node (ref "R132") (pin "1") (pinfunction "1_1") (pintype "passive"))
      (node (ref "U20") (pin "8") (pinfunction "VIN+_8") (pintype "input"))
    )
    (net (code "31") (name "Net-(U20-VIN-)") (class "Default")
      (node (ref "C150") (pin "1") (pinfunction "1_1") (pintype "passive"))
      (node (ref "C151") (pin "1") (pinfunction "1_1") (pintype "passive"))
      (node (ref "R124") (pin "1") (pinfunction "1_1") (pintype "passive"))
      (node (ref "R126") (pin "2") (pinfunction "2_2") (pintype "passive"))
      (node (ref "U20") (pin "1") (pinfunction "VIN-_1") (pintype "input"))
    )
    (net (code "32") (name "Net-(U20-VOUT+)") (class "Default")
      (node (ref "C150") (pin "2") (pinfunction "2_2") (pintype "passive"))
      (node (ref "R128") (pin "1") (pinfunction "1_1") (pintype "passive"))
      (node (ref "U20") (pin "4") (pinfunction "VOUT+_4") (pintype "output"))
    )
    (net (code "33") (name "Net-(U20-VOUT-)") (class "Default")
      (node (ref "C154") (pin "2") (pinfunction "2_2") (pintype "passive"))
      (node (ref "R130") (pin "1") (pinfunction "1_1") (pintype "passive"))
      (node (ref "U20") (pin "5") (pinfunction "VOUT-_5") (pintype "output"))
    )
    (net (code "34") (name "Net-(U20-~{PD})") (class "Default")
      (node (ref "R131") (pin "1") (pinfunction "1_1") (pintype "passive"))
      (node (ref "U20") (pin "7") (pinfunction "~{PD}_7") (pintype "input"))
    )
    (net (code "35") (name "Net-(U21-AIN1N)") (class "Default")
      (node (ref "C147") (pin "1") (pinfunction "1_1") (pintype "passive"))
      (node (ref "R118") (pin "2") (pinfunction "2_2") (pintype "passive"))
      (node (ref "U21") (pin "1") (pinfunction "AIN1N_1") (pintype "input"))
    )
    (net (code "36") (name "Net-(U21-AIN1P)") (class "Default")
      (node (ref "C147") (pin "2") (pinfunction "2_2") (pintype "passive"))
      (node (ref "R119") (pin "2") (pinfunction "2_2") (pintype "passive"))
      (node (ref "U21") (pin "2") (pinfunction "AIN1P_2") (pintype "input"))
    )
    (net (code "37") (name "Net-(U21-AIN2N)") (class "Default")
      (node (ref "C148") (pin "1") (pinfunction "1_1") (pintype "passive"))
      (node (ref "R125") (pin "2") (pinfunction "2_2") (pintype "passive"))
      (node (ref "U21") (pin "3") (pinfunction "AIN2N_3") (pintype "input"))
    )
    (net (code "38") (name "Net-(U21-AIN2P)") (class "Default")
      (node (ref "C148") (pin "2") (pinfunction "2_2") (pintype "passive"))
      (node (ref "R127") (pin "2") (pinfunction "2_2") (pintype "passive"))
      (node (ref "U21") (pin "4") (pinfunction "AIN2P_4") (pintype "input"))
    )
    (net (code "39") (name "Net-(U21-CAP)") (class "Default")
      (node (ref "C156") (pin "1") (pinfunction "1_1") (pintype "passive"))
      (node (ref "U21") (pin "28") (pinfunction "CAP_28") (pintype "passive"))
    )
    (net (code "40") (name "Net-(U21-CLKIN{slash}XTAL1)") (class "Default")
      (node (ref "R135") (pin "1") (pinfunction "1_1") (pintype "passive"))
      (node (ref "R137") (pin "2") (pinfunction "2_2") (pintype "passive"))
      (node (ref "U21") (pin "25") (pinfunction "CLKIN/XTAL1_25") (pintype "input"))
    )
    (net (code "41") (name "Net-(U21-M0)") (class "Default")
      (node (ref "R120") (pin "1") (pinfunction "1_1") (pintype "passive"))
      (node (ref "U21") (pin "30") (pinfunction "M0_30") (pintype "passive"))
    )
    (net (code "42") (name "Net-(U21-REFEXT)") (class "Default")
      (node (ref "C155") (pin "1") (pinfunction "1_1") (pintype "passive"))
      (node (ref "R133") (pin "2") (pinfunction "2_2") (pintype "passive"))
      (node (ref "U21") (pin "14") (pinfunction "REFEXT_14") (pintype "passive"))
    )
    (net (code "43") (name "Net-(U21-RESET)") (class "Default")
      (node (ref "C149") (pin "2") (pinfunction "2_2") (pintype "passive"))
      (node (ref "R121") (pin "1") (pinfunction "1_1") (pintype "passive"))
      (node (ref "S1") (pin "1") (pinfunction "1_1") (pintype "passive"))
      (node (ref "U21") (pin "17") (pinfunction "RESET_17") (pintype "input"))
    )
    (net (code "44") (name "Net-(U21-VREFP)") (class "Default")
      (node (ref "C145") (pin "2") (pinfunction "2_2") (pintype "passive"))
      (node (ref "C146") (pin "2") (pinfunction "2_2") (pintype "passive"))
      (node (ref "U21") (pin "12") (pinfunction "VREFP_12") (pintype "input"))
    )
    (net (code "45") (name "Net-(U21-XTAL2)") (class "Default")
      (node (ref "R136") (pin "2") (pinfunction "2_2") (pintype "passive"))
      (node (ref "R137") (pin "1") (pinfunction "1_1") (pintype "passive"))
      (node (ref "U21") (pin "26") (pinfunction "XTAL2_26") (pintype "output"))
    )
    (net (code "46") (name "Net-(U22A-TRIM{slash}NR)") (class "Default")
      (node (ref "C157") (pin "1") (pinfunction "1_1") (pintype "passive"))
      (node (ref "U22") (pin "5") (pinfunction "TRIM/NR_5") (pintype "input"))
    )
    (net (code "47") (name "Net-(U22A-VOUT)") (class "Default")
      (node (ref "C158") (pin "1") (pinfunction "1_1") (pintype "passive"))
      (node (ref "C159") (pin "1") (pinfunction "1_1") (pintype "passive"))
      (node (ref "R133") (pin "1") (pinfunction "1_1") (pintype "passive"))
      (node (ref "R134") (pin "2") (pinfunction "2_2") (pintype "passive"))
      (node (ref "U22") (pin "6") (pinfunction "VOUT_6") (pintype "output"))
      (node (ref "VREF_ADC") (pin "1") (pintype "passive"))
    )
    (net (code "48") (name "Vocm1") (class "Default")
      (node (ref "C131") (pin "1") (pinfunction "1_1") (pintype "passive"))
      (node (ref "U19") (pin "2") (pinfunction "VOCM_2") (pintype "input"))
    )
    (net (code "49") (name "Vocm2") (class "Default")
      (node (ref "C132") (pin "1") (pinfunction "1_1") (pintype "passive"))
      (node (ref "U20") (pin "2") (pinfunction "VOCM_2") (pintype "input"))
    )
    (net (code "50") (name "unconnected-(U21-NC-Pad24)") (class "Default")
      (node (ref "U21") (pin "24") (pinfunction "NC_24") (pintype "passive"))
    )
    (net (code "51") (name "unconnected-(U22A-TEMP-Pad3)") (class "Default")
      (node (ref "U22") (pin "3") (pinfunction "TEMP_3") (pintype "output"))
    )
  )
)
